# stabilizer.net
KiCad netlist of a schematic drawn in EAGLE
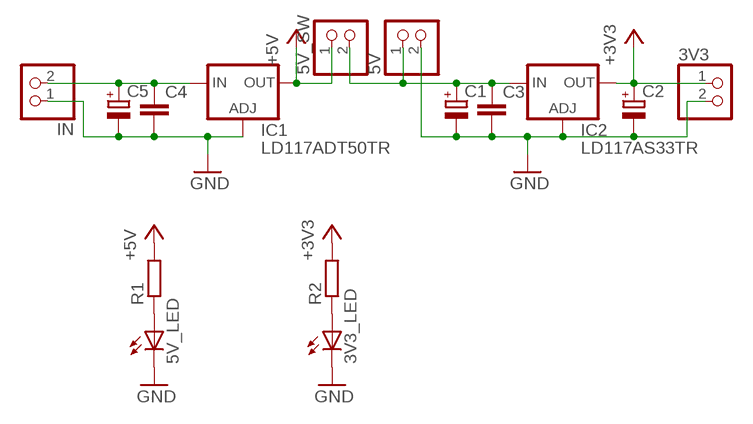
[diagram p0: schematic, sheet 1]

(export (version "E")
  (design (tool "Eeschema 10.0.6"))
  (components
    (comp (ref "3V3")
      (value "PINHD-1X2")
      (footprint "eagle-import:1X02")
      (libsource (lib "eagle-import") (part "PINHD-1X2"))
    )
    (comp (ref "3V3_LED")
      (value "LEDSML0805")
      (footprint "eagle-import:SML0805")
      (libsource (lib "eagle-import") (part "LEDSML0805"))
    )
    (comp (ref "5V")
      (value "PINHD-1X2")
      (footprint "eagle-import:1X02")
      (libsource (lib "eagle-import") (part "PINHD-1X2"))
    )
    (comp (ref "5V_LED")
      (value "LEDSML0805")
      (footprint "eagle-import:SML0805")
      (libsource (lib "eagle-import") (part "LEDSML0805"))
    )
    (comp (ref "5V_SW")
      (value "PINHD-1X2")
      (footprint "eagle-import:1X02")
      (libsource (lib "eagle-import") (part "PINHD-1X2"))
    )
    (comp (ref "C1")
      (value "CPOL-EUD")
      (footprint "eagle-import:PANASONIC_D")
      (libsource (lib "eagle-import") (part "CPOL-EUD"))
    )
    (comp (ref "C2")
      (value "CPOL-EUD")
      (footprint "eagle-import:PANASONIC_D")
      (libsource (lib "eagle-import") (part "CPOL-EUD"))
    )
    (comp (ref "C3")
      (value "C-EUC0805")
      (footprint "eagle-import:C0805")
      (libsource (lib "eagle-import") (part "C-EUC0805"))
    )
    (comp (ref "C4")
      (value "C-EUC0805")
      (footprint "eagle-import:C0805")
      (libsource (lib "eagle-import") (part "C-EUC0805"))
    )
    (comp (ref "C5")
      (value "CPOL-EUD")
      (footprint "eagle-import:PANASONIC_D")
      (libsource (lib "eagle-import") (part "CPOL-EUD"))
    )
    (comp (ref "IC1")
      (value "LD117ADT50TR")
      (footprint "eagle-import:DPACK")
      (libsource (lib "eagle-import") (part "LD117A?DT50TR"))
    )
    (comp (ref "IC2")
      (value "LD117AS33TR")
      (footprint "eagle-import:SOT223")
      (libsource (lib "eagle-import") (part "LD117A?S33TR"))
    )
    (comp (ref "IN")
      (value "PINHD-1X2")
      (footprint "eagle-import:1X02")
      (libsource (lib "eagle-import") (part "PINHD-1X2"))
    )
    (comp (ref "R1")
      (value "R-EU_R0805")
      (footprint "eagle-import:R0805")
      (libsource (lib "eagle-import") (part "R-EU_R0805"))
    )
    (comp (ref "R2")
      (value "R-EU_R0805")
      (footprint "eagle-import:R0805")
      (libsource (lib "eagle-import") (part "R-EU_R0805"))
    )
  )
  (nets
    (net (code "1") (name "+3V3") (class "Default")
      (node (ref "3V3") (pin "1") (pinfunction "1_1") (pintype "passive"))
      (node (ref "C2") (pin "+") (pinfunction "+_+") (pintype "passive"))
      (node (ref "IC2") (pin "4") (pinfunction "OUT_4") (pintype "passive"))
      (node (ref "R2") (pin "2") (pinfunction "2_2") (pintype "passive"))
    )
    (net (code "2") (name "+5V") (class "Default")
      (node (ref "5V_SW") (pin "1") (pinfunction "1_1") (pintype "passive"))
      (node (ref "IC1") (pin "4") (pinfunction "OUT_4") (pintype "passive"))
      (node (ref "R1") (pin "2") (pinfunction "2_2") (pintype "passive"))
    )
    (net (code "3") (name "GND") (class "Default")
      (node (ref "3V3") (pin "2") (pinfunction "2_2") (pintype "passive"))
      (node (ref "3V3_LED") (pin "C") (pinfunction "C_C") (pintype "passive"))
      (node (ref "5V") (pin "2") (pinfunction "2_2") (pintype "passive"))
      (node (ref "5V_LED") (pin "C") (pinfunction "C_C") (pintype "passive"))
      (node (ref "C1") (pin "-") (pinfunction "-_-") (pintype "passive"))
      (node (ref "C2") (pin "-") (pinfunction "-_-") (pintype "passive"))
      (node (ref "C3") (pin "2") (pinfunction "2_2") (pintype "passive"))
      (node (ref "C4") (pin "2") (pinfunction "2_2") (pintype "passive"))
      (node (ref "C5") (pin "-") (pinfunction "-_-") (pintype "passive"))
      (node (ref "IC1") (pin "1") (pinfunction "ADJ_1") (pintype "input"))
      (node (ref "IC2") (pin "1") (pinfunction "ADJ_1") (pintype "input"))
      (node (ref "IN") (pin "1") (pinfunction "1_1") (pintype "passive"))
    )
    (net (code "4") (name "Net-(3V3_LED-PadA)") (class "Default")
      (node (ref "3V3_LED") (pin "A") (pinfunction "A_A") (pintype "passive"))
      (node (ref "R2") (pin "1") (pinfunction "1_1") (pintype "passive"))
    )
    (net (code "5") (name "Net-(5V_LED-PadA)") (class "Default")
      (node (ref "5V_LED") (pin "A") (pinfunction "A_A") (pintype "passive"))
      (node (ref "R1") (pin "1") (pinfunction "1_1") (pintype "passive"))
    )
    (net (code "6") (name "Net-(IC1-IN)") (class "Default")
      (node (ref "C4") (pin "1") (pinfunction "1_1") (pintype "passive"))
      (node (ref "C5") (pin "+") (pinfunction "+_+") (pintype "passive"))
      (node (ref "IC1") (pin "3") (pinfunction "IN_3") (pintype "input"))
      (node (ref "IN") (pin "2") (pinfunction "2_2") (pintype "passive"))
    )
    (net (code "7") (name "Net-(IC2-IN)") (class "Default")
      (node (ref "5V") (pin "1") (pinfunction "1_1") (pintype "passive"))
      (node (ref "5V_SW") (pin "2") (pinfunction "2_2") (pintype "passive"))
      (node (ref "C1") (pin "+") (pinfunction "+_+") (pintype "passive"))
      (node (ref "C3") (pin "1") (pinfunction "1_1") (pintype "passive"))
      (node (ref "IC2") (pin "3") (pinfunction "IN_3") (pintype "input"))
    )
  )
)
